# spectrum_4kHz_125Hz.net
KiCad netlist of a schematic drawn in Altium Designer
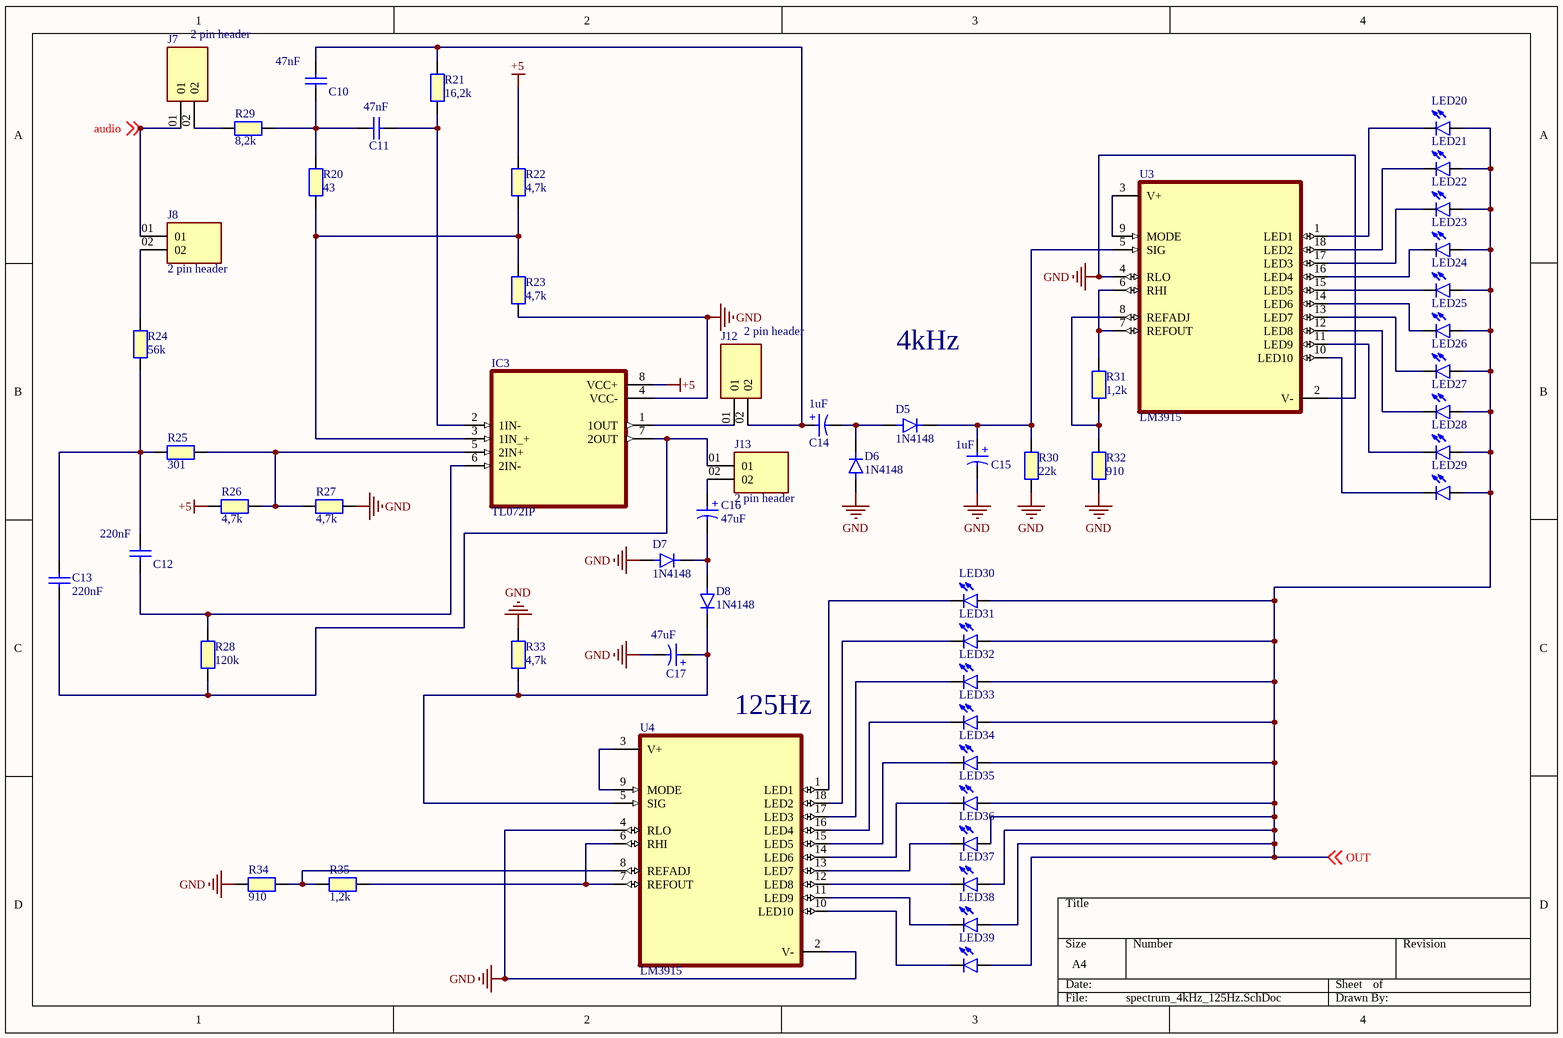
[diagram p0: spectrum_4kHz_125Hz.SchDoc]

(export (version "E")
  (design (tool "Eeschema 10.0.6"))
  (components
    (comp (ref "C10")
      (value "47nF")
      (footprint "CAPC2012X65N")
      (description "47nF ceramic")
      (fields
        (field (name "MANUFACTURER PART NUMBER") "885012004008")
        (field (name "MANUFACTURER") "Wurth Elektronik")
      )
      (libsource (lib "SpectrumComponents") (part "885012004008"))
    )
    (comp (ref "C11")
      (value "47nF")
      (footprint "CAPC2012X65N")
      (description "47nF ceramic")
      (fields
        (field (name "MANUFACTURER PART NUMBER") "885012004008")
        (field (name "MANUFACTURER") "Wurth Elektronik")
      )
      (libsource (lib "SpectrumComponents") (part "885012004008"))
    )
    (comp (ref "C12")
      (value "220nF")
      (footprint "CAPC2012X65N")
      (description "220nF ceramic")
      (fields
        (field (name "MANUFACTURER PART NUMBER") "885012004008")
        (field (name "MANUFACTURER") "Wurth Elektronik")
      )
      (libsource (lib "SpectrumComponents") (part "885012004008"))
    )
    (comp (ref "C13")
      (value "220nF")
      (footprint "CAPC2012X65N")
      (description "220nF ceramic")
      (fields
        (field (name "MANUFACTURER PART NUMBER") "885012004008")
        (field (name "MANUFACTURER") "Wurth Elektronik")
      )
      (libsource (lib "SpectrumComponents") (part "885012004008"))
    )
    (comp (ref "C14")
      (value "1uF")
      (footprint "WCAP-ATG8_D5H11")
      (description "Elco 1uF")
      (fields
        (field (name "MANUFACTURER PART NUMBER") "860010272005")
        (field (name "MANUFACTURER") "Wurth Elektronik")
      )
      (libsource (lib "SpectrumComponents") (part "860010272005"))
    )
    (comp (ref "C15")
      (value "1uF")
      (footprint "WCAP-ATG8_D5H11")
      (description "WCAP-ATG8 Aluminum Electrolytic Capacitor, Radial, THT, D5 x H11mm, 1uF, 10V")
      (fields
        (field (name "MANUFACTURER PART NUMBER") "860010272005")
        (field (name "MANUFACTURER") "Wurth Elektronik")
      )
      (libsource (lib "SpectrumComponents") (part "860010272005"))
    )
    (comp (ref "C16")
      (value "47uF")
      (footprint "WCAP-ATG8_D5H11")
      (description "Elco 47uF")
      (fields
        (field (name "MANUFACTURER PART NUMBER") "860010272005")
        (field (name "MANUFACTURER") "Wurth Elektronik")
      )
      (libsource (lib "SpectrumComponents") (part "860010272005"))
    )
    (comp (ref "C17")
      (value "47uF")
      (footprint "WCAP-ATG8_D5H11")
      (description "WCAP-ATG8 Aluminum Electrolytic Capacitor, Radial, THT, D5 x H11mm, 47µF, 10V")
      (fields
        (field (name "MANUFACTURER PART NUMBER") "860010272005")
        (field (name "MANUFACTURER") "Wurth Elektronik")
      )
      (libsource (lib "SpectrumComponents") (part "860010272005"))
    )
    (comp (ref "D5")
      (value "1N4148")
      (footprint "DIOAD829W49L456D191")
      (description "Diode Standard 75V 200mA Surface Mount SOD-523F")
      (fields (field (name "MF") "ON Semiconductor"))
      (libsource (lib "SpectrumComponents") (part "1N4148"))
    )
    (comp (ref "D6")
      (value "1N4148")
      (footprint "DIOAD829W49L456D191")
      (description "Diode Standard 75V 200mA Surface Mount SOD-523F")
      (fields (field (name "MF") "ON Semiconductor"))
      (libsource (lib "SpectrumComponents") (part "1N4148"))
    )
    (comp (ref "D7")
      (value "1N4148")
      (footprint "DIOAD829W49L456D191")
      (description "Diode Standard 75V 200mA Surface Mount SOD-523F")
      (fields (field (name "MF") "ON Semiconductor"))
      (libsource (lib "SpectrumComponents") (part "1N4148"))
    )
    (comp (ref "D8")
      (value "1N4148")
      (footprint "DIOAD829W49L456D191")
      (description "Diode Standard 75V 200mA Surface Mount SOD-523F")
      (fields (field (name "MF") "ON Semiconductor"))
      (libsource (lib "SpectrumComponents") (part "1N4148"))
    )
    (comp (ref "IC3")
      (value "TL072IP")
      (footprint "DIP794W45P254L959H508Q8")
      (description "Dual, 30-V, 3-MHz, high slew rate (13-V/Âµs), In to V+, JFET-input op amp")
      (fields (field (name "MF") "Texas Instruments"))
      (libsource (lib "SpectrumComponents") (part "TL072IP"))
    )
    (comp (ref "J7")
      (value "2 pin header")
      (footprint "SpectrumComponents:SAMTEC_HTSW-102-07-TM-S")
      (description "2 pin header Jumper")
      (fields (field (name "MP") "HTSW10207TMS") (field (name "MF") "Samtec"))
      (libsource (lib "") (part "2 pin header_1"))
    )
    (comp (ref "J8")
      (value "2 pin header")
      (footprint "SpectrumComponents:SAMTEC_HTSW-102-07-TM-S")
      (description "2 pin header Jumper")
      (fields (field (name "MP") "HTSW10207TMS") (field (name "MF") "Samtec"))
      (libsource (lib "SpectrumComponents") (part "2 pin header"))
    )
    (comp (ref "J12")
      (value "2 pin header")
      (footprint "SpectrumComponents:SAMTEC_HTSW-102-07-TM-S")
      (description "2 pin header Jumper")
      (fields (field (name "MP") "HTSW10207TMS") (field (name "MF") "Samtec"))
      (libsource (lib "") (part "2 pin header_1"))
    )
    (comp (ref "J13")
      (value "2 pin header")
      (footprint "SpectrumComponents:SAMTEC_HTSW-102-07-TM-S")
      (description "2 pin header Jumper")
      (fields (field (name "MP") "HTSW10207TMS") (field (name "MF") "Samtec"))
      (libsource (lib "SpectrumComponents") (part "2 pin header"))
    )
    (comp (ref "LED20")
      (value "LED 2x3x4")
      (footprint "LED 2x3x4mm")
      (description "Green 569nm LED Indication - Discrete 1.9V Radial")
      (fields (field (name "MP") "TLLG4400") (field (name "MF") "Vishay Semiconductors"))
      (libsource (lib "SpectrumComponents") (part "LED 2x3x4"))
    )
    (comp (ref "LED21")
      (value "LED 2x3x4")
      (footprint "LED 2x3x4mm")
      (description "Green 569nm LED Indication - Discrete 1.9V Radial")
      (fields (field (name "MP") "TLLG4400") (field (name "MF") "Vishay Semiconductors"))
      (libsource (lib "SpectrumComponents") (part "LED 2x3x4"))
    )
    (comp (ref "LED22")
      (value "LED 2x3x4")
      (footprint "LED 2x3x4mm")
      (description "Green 569nm LED Indication - Discrete 1.9V Radial")
      (fields (field (name "MP") "TLLG4400") (field (name "MF") "Vishay Semiconductors"))
      (libsource (lib "SpectrumComponents") (part "LED 2x3x4"))
    )
    (comp (ref "LED23")
      (value "LED 2x3x4")
      (footprint "LED 2x3x4mm")
      (description "Green 569nm LED Indication - Discrete 1.9V Radial")
      (fields (field (name "MP") "TLLG4400") (field (name "MF") "Vishay Semiconductors"))
      (libsource (lib "SpectrumComponents") (part "LED 2x3x4"))
    )
    (comp (ref "LED24")
      (value "LED 2x3x4")
      (footprint "LED 2x3x4mm")
      (description "Green 569nm LED Indication - Discrete 1.9V Radial")
      (fields (field (name "MP") "TLLG4400") (field (name "MF") "Vishay Semiconductors"))
      (libsource (lib "SpectrumComponents") (part "LED 2x3x4"))
    )
    (comp (ref "LED25")
      (value "LED 2x3x4")
      (footprint "LED 2x3x4mm")
      (description "Green 569nm LED Indication - Discrete 1.9V Radial")
      (fields (field (name "MP") "TLLG4400") (field (name "MF") "Vishay Semiconductors"))
      (libsource (lib "SpectrumComponents") (part "LED 2x3x4"))
    )
    (comp (ref "LED26")
      (value "LED 2x3x4")
      (footprint "LED 2x3x4mm")
      (description "Green 569nm LED Indication - Discrete 1.9V Radial")
      (fields (field (name "MP") "TLLG4400") (field (name "MF") "Vishay Semiconductors"))
      (libsource (lib "SpectrumComponents") (part "LED 2x3x4"))
    )
    (comp (ref "LED27")
      (value "LED 2x3x4")
      (footprint "LED 2x3x4mm")
      (description "Green 569nm LED Indication - Discrete 1.9V Radial")
      (fields (field (name "MP") "TLLG4400") (field (name "MF") "Vishay Semiconductors"))
      (libsource (lib "SpectrumComponents") (part "LED 2x3x4"))
    )
    (comp (ref "LED28")
      (value "LED 2x3x4")
      (footprint "LED 2x3x4mm")
      (description "Green 569nm LED Indication - Discrete 1.9V Radial")
      (fields (field (name "MP") "TLLG4400") (field (name "MF") "Vishay Semiconductors"))
      (libsource (lib "SpectrumComponents") (part "LED 2x3x4"))
    )
    (comp (ref "LED29")
      (value "LED 2x3x4")
      (footprint "LED 2x3x4mm")
      (description "Green 569nm LED Indication - Discrete 1.9V Radial")
      (fields (field (name "MP") "TLLG4400") (field (name "MF") "Vishay Semiconductors"))
      (libsource (lib "SpectrumComponents") (part "LED 2x3x4"))
    )
    (comp (ref "LED30")
      (value "LED 2x3x4")
      (footprint "LED 2x3x4mm")
      (description "Green 569nm LED Indication - Discrete 1.9V Radial")
      (fields (field (name "MP") "TLLG4400") (field (name "MF") "Vishay Semiconductors"))
      (libsource (lib "SpectrumComponents") (part "LED 2x3x4"))
    )
    (comp (ref "LED31")
      (value "LED 2x3x4")
      (footprint "LED 2x3x4mm")
      (description "Green 569nm LED Indication - Discrete 1.9V Radial")
      (fields (field (name "MP") "TLLG4400") (field (name "MF") "Vishay Semiconductors"))
      (libsource (lib "SpectrumComponents") (part "LED 2x3x4"))
    )
    (comp (ref "LED32")
      (value "LED 2x3x4")
      (footprint "LED 2x3x4mm")
      (description "Green 569nm LED Indication - Discrete 1.9V Radial")
      (fields (field (name "MP") "TLLG4400") (field (name "MF") "Vishay Semiconductors"))
      (libsource (lib "SpectrumComponents") (part "LED 2x3x4"))
    )
    (comp (ref "LED33")
      (value "LED 2x3x4")
      (footprint "LED 2x3x4mm")
      (description "Green 569nm LED Indication - Discrete 1.9V Radial")
      (fields (field (name "MP") "TLLG4400") (field (name "MF") "Vishay Semiconductors"))
      (libsource (lib "SpectrumComponents") (part "LED 2x3x4"))
    )
    (comp (ref "LED34")
      (value "LED 2x3x4")
      (footprint "LED 2x3x4mm")
      (description "Green 569nm LED Indication - Discrete 1.9V Radial")
      (fields (field (name "MP") "TLLG4400") (field (name "MF") "Vishay Semiconductors"))
      (libsource (lib "SpectrumComponents") (part "LED 2x3x4"))
    )
    (comp (ref "LED35")
      (value "LED 2x3x4")
      (footprint "LED 2x3x4mm")
      (description "Green 569nm LED Indication - Discrete 1.9V Radial")
      (fields (field (name "MP") "TLLG4400") (field (name "MF") "Vishay Semiconductors"))
      (libsource (lib "SpectrumComponents") (part "LED 2x3x4"))
    )
    (comp (ref "LED36")
      (value "LED 2x3x4")
      (footprint "LED 2x3x4mm")
      (description "Green 569nm LED Indication - Discrete 1.9V Radial")
      (fields (field (name "MP") "TLLG4400") (field (name "MF") "Vishay Semiconductors"))
      (libsource (lib "SpectrumComponents") (part "LED 2x3x4"))
    )
    (comp (ref "LED37")
      (value "LED 2x3x4")
      (footprint "LED 2x3x4mm")
      (description "Green 569nm LED Indication - Discrete 1.9V Radial")
      (fields (field (name "MP") "TLLG4400") (field (name "MF") "Vishay Semiconductors"))
      (libsource (lib "SpectrumComponents") (part "LED 2x3x4"))
    )
    (comp (ref "LED38")
      (value "LED 2x3x4")
      (footprint "LED 2x3x4mm")
      (description "Green 569nm LED Indication - Discrete 1.9V Radial")
      (fields (field (name "MP") "TLLG4400") (field (name "MF") "Vishay Semiconductors"))
      (libsource (lib "SpectrumComponents") (part "LED 2x3x4"))
    )
    (comp (ref "LED39")
      (value "LED 2x3x4")
      (footprint "LED 2x3x4mm")
      (description "Green 569nm LED Indication - Discrete 1.9V Radial")
      (fields (field (name "MP") "TLLG4400") (field (name "MF") "Vishay Semiconductors"))
      (libsource (lib "SpectrumComponents") (part "LED 2x3x4"))
    )
    (comp (ref "R20")
      (value "43")
      (footprint "RESC2012X50N")
      (description "43Ohm Resistor 0805")
      (fields (field (name "PART NUMBER") "TNPW080510K0BETA") (field (name "MANUFACTURER") "Vishay Dale"))
      (libsource (lib "") (part "RESISTOR 0805_1"))
    )
    (comp (ref "R21")
      (value "16,2k")
      (footprint "RESC2012X50N")
      (description "16,2k Resistor 0805")
      (fields (field (name "PART NUMBER") "TNPW080510K0BETA") (field (name "MANUFACTURER") "Vishay Dale"))
      (libsource (lib "") (part "RESISTOR 0805_1"))
    )
    (comp (ref "R22")
      (value "4,7k")
      (footprint "RESC2012X50N")
      (description "4,7k Resistor 0805")
      (fields (field (name "PART NUMBER") "TNPW080510K0BETA") (field (name "MANUFACTURER") "Vishay Dale"))
      (libsource (lib "") (part "RESISTOR 0805_1"))
    )
    (comp (ref "R23")
      (value "4,7k")
      (footprint "RESC2012X50N")
      (description "4,7k Resistor 0805")
      (fields (field (name "PART NUMBER") "TNPW080510K0BETA") (field (name "MANUFACTURER") "Vishay Dale"))
      (libsource (lib "") (part "RESISTOR 0805_1"))
    )
    (comp (ref "R24")
      (value "56k")
      (footprint "RESC2012X50N")
      (description "75k Resistor 0805")
      (fields (field (name "PART NUMBER") "TNPW080510K0BETA") (field (name "MANUFACTURER") "Vishay Dale"))
      (libsource (lib "") (part "RESISTOR 0805_1"))
    )
    (comp (ref "R25")
      (value "301")
      (footprint "RESC2012X50N")
      (description "301 Resistor 0805")
      (fields (field (name "PART NUMBER") "TNPW080510K0BETA") (field (name "MANUFACTURER") "Vishay Dale"))
      (libsource (lib "") (part "RESISTOR 0805_2"))
    )
    (comp (ref "R26")
      (value "4,7k")
      (footprint "RESC2012X50N")
      (description "4,7k Resistor 0805")
      (fields (field (name "PART NUMBER") "TNPW080510K0BETA") (field (name "MANUFACTURER") "Vishay Dale"))
      (libsource (lib "") (part "RESISTOR 0805_2"))
    )
    (comp (ref "R27")
      (value "4,7k")
      (footprint "RESC2012X50N")
      (description "4,7k Resistor 0805")
      (fields (field (name "PART NUMBER") "TNPW080510K0BETA") (field (name "MANUFACTURER") "Vishay Dale"))
      (libsource (lib "") (part "RESISTOR 0805_3"))
    )
    (comp (ref "R28")
      (value "120k")
      (footprint "RESC2012X50N")
      (description "120k Resistor 0805")
      (fields (field (name "PART NUMBER") "TNPW080510K0BETA") (field (name "MANUFACTURER") "Vishay Dale"))
      (libsource (lib "") (part "RESISTOR 0805_1"))
    )
    (comp (ref "R29")
      (value "8,2k")
      (footprint "RESC2012X50N")
      (description "8,2k Resistor 0805")
      (fields (field (name "PART NUMBER") "TNPW080510K0BETA") (field (name "MANUFACTURER") "Vishay Dale"))
      (libsource (lib "") (part "RESISTOR 0805_3"))
    )
    (comp (ref "R30")
      (value "22k")
      (footprint "RESC2012X50N")
      (description "22k Resistor 0805")
      (fields (field (name "PART NUMBER") "TNPW080510K0BETA") (field (name "MANUFACTURER") "Vishay Dale"))
      (libsource (lib "") (part "RESISTOR 0805_1"))
    )
    (comp (ref "R31")
      (value "1,2k")
      (footprint "RESC2012X50N")
      (description "1,2k Resistor 0805")
      (fields (field (name "PART NUMBER") "TNPW080510K0BETA") (field (name "MANUFACTURER") "Vishay Dale"))
      (libsource (lib "SpectrumComponents") (part "RESISTOR 0805"))
    )
    (comp (ref "R32")
      (value "910")
      (footprint "RESC2012X50N")
      (description "910 Resistor 0805")
      (fields (field (name "PART NUMBER") "TNPW080510K0BETA") (field (name "MANUFACTURER") "Vishay Dale"))
      (libsource (lib "SpectrumComponents") (part "RESISTOR 0805"))
    )
    (comp (ref "R33")
      (value "4,7k")
      (footprint "RESC2012X50N")
      (description "4,7k Resistor 0805")
      (fields (field (name "PART NUMBER") "TNPW080510K0BETA") (field (name "MANUFACTURER") "Vishay Dale"))
      (libsource (lib "SpectrumComponents") (part "RESISTOR 0805"))
    )
    (comp (ref "R34")
      (value "910")
      (footprint "RESC2012X50N")
      (description "910 Resistor 0805")
      (fields (field (name "PART NUMBER") "TNPW080510K0BETA") (field (name "MANUFACTURER") "Vishay Dale"))
      (libsource (lib "") (part "RESISTOR 0805_2"))
    )
    (comp (ref "R35")
      (value "1,2k")
      (footprint "RESC2012X50N")
      (description "1,2k Resistor 0805")
      (fields (field (name "PART NUMBER") "TNPW080510K0BETA") (field (name "MANUFACTURER") "Vishay Dale"))
      (libsource (lib "") (part "RESISTOR 0805_2"))
    )
    (comp (ref "U3")
      (value "LM3915")
      (footprint "SpectrumComponents:DIP952W45P254L2336H533Q18")
      (fields (field (name "MP") "LM3914N-1"))
      (libsource (lib "SpectrumComponents") (part "LM3915"))
    )
    (comp (ref "U4")
      (value "LM3915")
      (footprint "SpectrumComponents:DIP952W45P254L2336H533Q18")
      (fields (field (name "MP") "LM3914N-1"))
      (libsource (lib "SpectrumComponents") (part "LM3915"))
    )
  )
  (nets
    (net (code "1") (name "+5") (class "Default")
      (node (ref "IC3") (pin "8") (pinfunction "VCC+_8") (pintype "power_in"))
      (node (ref "R22") (pin "2") (pinfunction "2_2") (pintype "passive"))
      (node (ref "R26") (pin "2") (pinfunction "2_2") (pintype "passive"))
    )
    (net (code "2") (name "GND") (class "Default")
      (node (ref "C15") (pin "2") (pinfunction "N_2") (pintype "passive"))
      (node (ref "C17") (pin "2") (pinfunction "N_2") (pintype "passive"))
      (node (ref "D6") (pin "A") (pinfunction "A_A") (pintype "passive"))
      (node (ref "D7") (pin "A") (pinfunction "A_A") (pintype "passive"))
      (node (ref "IC3") (pin "4") (pinfunction "VCC-_4") (pintype "power_in"))
      (node (ref "R23") (pin "1") (pinfunction "1_1") (pintype "passive"))
      (node (ref "R27") (pin "2") (pinfunction "2_2") (pintype "passive"))
      (node (ref "R30") (pin "1") (pinfunction "1_1") (pintype "passive"))
      (node (ref "R32") (pin "2") (pinfunction "2_2") (pintype "passive"))
      (node (ref "R33") (pin "1") (pinfunction "1_1") (pintype "passive"))
      (node (ref "R34") (pin "2") (pinfunction "2_2") (pintype "passive"))
      (node (ref "U3") (pin "2") (pinfunction "V-_2") (pintype "power_in"))
      (node (ref "U3") (pin "4") (pinfunction "RLO_4") (pintype "bidirectional"))
      (node (ref "U4") (pin "2") (pinfunction "V-_2") (pintype "power_in"))
      (node (ref "U4") (pin "4") (pinfunction "RLO_4") (pintype "bidirectional"))
    )
    (net (code "3") (name "Net-(C10-Pad1)") (class "Default")
      (node (ref "C10") (pin "1") (pinfunction "1_1") (pintype "passive"))
      (node (ref "C11") (pin "1") (pinfunction "1_1") (pintype "passive"))
      (node (ref "R20") (pin "2") (pinfunction "2_2") (pintype "passive"))
      (node (ref "R29") (pin "2") (pinfunction "2_2") (pintype "passive"))
    )
    (net (code "4") (name "Net-(C12-Pad2)") (class "Default")
      (node (ref "C12") (pin "2") (pinfunction "2_2") (pintype "passive"))
      (node (ref "C13") (pin "2") (pinfunction "2_2") (pintype "passive"))
      (node (ref "R24") (pin "1") (pinfunction "1_1") (pintype "passive"))
      (node (ref "R25") (pin "2") (pinfunction "2_2") (pintype "passive"))
    )
    (net (code "5") (name "Net-(C14-N)") (class "Default")
      (node (ref "C14") (pin "2") (pinfunction "N_2") (pintype "passive"))
      (node (ref "D5") (pin "A") (pinfunction "A_A") (pintype "passive"))
      (node (ref "D6") (pin "C") (pinfunction "C_C") (pintype "passive"))
    )
    (net (code "6") (name "Net-(C14-P)") (class "Default")
      (node (ref "C10") (pin "2") (pinfunction "2_2") (pintype "passive"))
      (node (ref "C14") (pin "1") (pinfunction "P_1") (pintype "passive"))
      (node (ref "J12") (pin "02") (pinfunction "02_02") (pintype "passive"))
      (node (ref "R21") (pin "2") (pinfunction "2_2") (pintype "passive"))
    )
    (net (code "7") (name "Net-(C15-P)") (class "Default")
      (node (ref "C15") (pin "1") (pinfunction "P_1") (pintype "passive"))
      (node (ref "D5") (pin "C") (pinfunction "C_C") (pintype "passive"))
      (node (ref "R30") (pin "2") (pinfunction "2_2") (pintype "passive"))
      (node (ref "U3") (pin "5") (pinfunction "SIG_5") (pintype "input"))
    )
    (net (code "8") (name "Net-(C16-N)") (class "Default")
      (node (ref "C16") (pin "2") (pinfunction "N_2") (pintype "passive"))
      (node (ref "D7") (pin "C") (pinfunction "C_C") (pintype "passive"))
      (node (ref "D8") (pin "A") (pinfunction "A_A") (pintype "passive"))
    )
    (net (code "9") (name "Net-(C16-P)") (class "Default")
      (node (ref "C16") (pin "1") (pinfunction "P_1") (pintype "passive"))
      (node (ref "J13") (pin "02") (pinfunction "02_02") (pintype "passive"))
    )
    (net (code "10") (name "Net-(C17-P)") (class "Default")
      (node (ref "C17") (pin "1") (pinfunction "P_1") (pintype "passive"))
      (node (ref "D8") (pin "C") (pinfunction "C_C") (pintype "passive"))
      (node (ref "R33") (pin "2") (pinfunction "2_2") (pintype "passive"))
      (node (ref "U4") (pin "5") (pinfunction "SIG_5") (pintype "input"))
    )
    (net (code "11") (name "Net-(IC3-1IN-)") (class "Default")
      (node (ref "C11") (pin "2") (pinfunction "2_2") (pintype "passive"))
      (node (ref "IC3") (pin "2") (pinfunction "1IN-_2") (pintype "input"))
      (node (ref "R21") (pin "1") (pinfunction "1_1") (pintype "passive"))
    )
    (net (code "12") (name "Net-(IC3-1IN_+)") (class "Default")
      (node (ref "IC3") (pin "3") (pinfunction "1IN_+_3") (pintype "input"))
      (node (ref "R20") (pin "1") (pinfunction "1_1") (pintype "passive"))
      (node (ref "R22") (pin "1") (pinfunction "1_1") (pintype "passive"))
      (node (ref "R23") (pin "2") (pinfunction "2_2") (pintype "passive"))
    )
    (net (code "13") (name "Net-(IC3-1OUT)") (class "Default")
      (node (ref "IC3") (pin "1") (pinfunction "1OUT_1") (pintype "output"))
      (node (ref "J12") (pin "01") (pinfunction "01_01") (pintype "passive"))
    )
    (net (code "14") (name "Net-(IC3-2IN+)") (class "Default")
      (node (ref "IC3") (pin "5") (pinfunction "2IN+_5") (pintype "input"))
      (node (ref "R25") (pin "1") (pinfunction "1_1") (pintype "passive"))
      (node (ref "R26") (pin "1") (pinfunction "1_1") (pintype "passive"))
      (node (ref "R27") (pin "1") (pinfunction "1_1") (pintype "passive"))
    )
    (net (code "15") (name "Net-(IC3-2IN-)") (class "Default")
      (node (ref "C12") (pin "1") (pinfunction "1_1") (pintype "passive"))
      (node (ref "IC3") (pin "6") (pinfunction "2IN-_6") (pintype "input"))
      (node (ref "R28") (pin "2") (pinfunction "2_2") (pintype "passive"))
    )
    (net (code "16") (name "Net-(IC3-2OUT)") (class "Default")
      (node (ref "C13") (pin "1") (pinfunction "1_1") (pintype "passive"))
      (node (ref "IC3") (pin "7") (pinfunction "2OUT_7") (pintype "output"))
      (node (ref "J13") (pin "01") (pinfunction "01_01") (pintype "passive"))
      (node (ref "R28") (pin "1") (pinfunction "1_1") (pintype "passive"))
    )
    (net (code "17") (name "Net-(J7-Pad02)") (class "Default")
      (node (ref "J7") (pin "02") (pinfunction "02_02") (pintype "passive"))
      (node (ref "R29") (pin "1") (pinfunction "1_1") (pintype "passive"))
    )
    (net (code "18") (name "Net-(J8-Pad02)") (class "Default")
      (node (ref "J8") (pin "02") (pinfunction "02_02") (pintype "passive"))
      (node (ref "R24") (pin "2") (pinfunction "2_2") (pintype "passive"))
    )
    (net (code "19") (name "Net-(LED20-C)") (class "Default")
      (node (ref "LED20") (pin "K") (pinfunction "C_K") (pintype "passive"))
      (node (ref "U3") (pin "1") (pinfunction "LED1_1") (pintype "bidirectional"))
    )
    (net (code "20") (name "Net-(LED21-C)") (class "Default")
      (node (ref "LED21") (pin "K") (pinfunction "C_K") (pintype "passive"))
      (node (ref "U3") (pin "18") (pinfunction "LED2_18") (pintype "bidirectional"))
    )
    (net (code "21") (name "Net-(LED22-C)") (class "Default")
      (node (ref "LED22") (pin "K") (pinfunction "C_K") (pintype "passive"))
      (node (ref "U3") (pin "17") (pinfunction "LED3_17") (pintype "bidirectional"))
    )
    (net (code "22") (name "Net-(LED23-C)") (class "Default")
      (node (ref "LED23") (pin "K") (pinfunction "C_K") (pintype "passive"))
      (node (ref "U3") (pin "16") (pinfunction "LED4_16") (pintype "bidirectional"))
    )
    (net (code "23") (name "Net-(LED24-C)") (class "Default")
      (node (ref "LED24") (pin "K") (pinfunction "C_K") (pintype "passive"))
      (node (ref "U3") (pin "15") (pinfunction "LED5_15") (pintype "bidirectional"))
    )
    (net (code "24") (name "Net-(LED25-C)") (class "Default")
      (node (ref "LED25") (pin "K") (pinfunction "C_K") (pintype "passive"))
      (node (ref "U3") (pin "14") (pinfunction "LED6_14") (pintype "bidirectional"))
    )
    (net (code "25") (name "Net-(LED26-C)") (class "Default")
      (node (ref "LED26") (pin "K") (pinfunction "C_K") (pintype "passive"))
      (node (ref "U3") (pin "13") (pinfunction "LED7_13") (pintype "bidirectional"))
    )
    (net (code "26") (name "Net-(LED27-C)") (class "Default")
      (node (ref "LED27") (pin "K") (pinfunction "C_K") (pintype "passive"))
      (node (ref "U3") (pin "12") (pinfunction "LED8_12") (pintype "bidirectional"))
    )
    (net (code "27") (name "Net-(LED28-C)") (class "Default")
      (node (ref "LED28") (pin "K") (pinfunction "C_K") (pintype "passive"))
      (node (ref "U3") (pin "11") (pinfunction "LED9_11") (pintype "bidirectional"))
    )
    (net (code "28") (name "Net-(LED29-C)") (class "Default")
      (node (ref "LED29") (pin "K") (pinfunction "C_K") (pintype "passive"))
      (node (ref "U3") (pin "10") (pinfunction "LED10_10") (pintype "bidirectional"))
    )
    (net (code "29") (name "Net-(LED30-C)") (class "Default")
      (node (ref "LED30") (pin "K") (pinfunction "C_K") (pintype "passive"))
      (node (ref "U4") (pin "1") (pinfunction "LED1_1") (pintype "bidirectional"))
    )
    (net (code "30") (name "Net-(LED31-C)") (class "Default")
      (node (ref "LED31") (pin "K") (pinfunction "C_K") (pintype "passive"))
      (node (ref "U4") (pin "18") (pinfunction "LED2_18") (pintype "bidirectional"))
    )
    (net (code "31") (name "Net-(LED32-C)") (class "Default")
      (node (ref "LED32") (pin "K") (pinfunction "C_K") (pintype "passive"))
      (node (ref "U4") (pin "17") (pinfunction "LED3_17") (pintype "bidirectional"))
    )
    (net (code "32") (name "Net-(LED33-C)") (class "Default")
      (node (ref "LED33") (pin "K") (pinfunction "C_K") (pintype "passive"))
      (node (ref "U4") (pin "16") (pinfunction "LED4_16") (pintype "bidirectional"))
    )
    (net (code "33") (name "Net-(LED34-C)") (class "Default")
      (node (ref "LED34") (pin "K") (pinfunction "C_K") (pintype "passive"))
      (node (ref "U4") (pin "15") (pinfunction "LED5_15") (pintype "bidirectional"))
    )
    (net (code "34") (name "Net-(LED35-C)") (class "Default")
      (node (ref "LED35") (pin "K") (pinfunction "C_K") (pintype "passive"))
      (node (ref "U4") (pin "14") (pinfunction "LED6_14") (pintype "bidirectional"))
    )
    (net (code "35") (name "Net-(LED36-C)") (class "Default")
      (node (ref "LED36") (pin "K") (pinfunction "C_K") (pintype "passive"))
      (node (ref "U4") (pin "13") (pinfunction "LED7_13") (pintype "bidirectional"))
    )
    (net (code "36") (name "Net-(LED37-C)") (class "Default")
      (node (ref "LED37") (pin "K") (pinfunction "C_K") (pintype "passive"))
      (node (ref "U4") (pin "12") (pinfunction "LED8_12") (pintype "bidirectional"))
    )
    (net (code "37") (name "Net-(LED38-C)") (class "Default")
      (node (ref "LED38") (pin "K") (pinfunction "C_K") (pintype "passive"))
      (node (ref "U4") (pin "11") (pinfunction "LED9_11") (pintype "bidirectional"))
    )
    (net (code "38") (name "Net-(LED39-C)") (class "Default")
      (node (ref "LED39") (pin "K") (pinfunction "C_K") (pintype "passive"))
      (node (ref "U4") (pin "10") (pinfunction "LED10_10") (pintype "bidirectional"))
    )
    (net (code "39") (name "Net-(U3-MODE)") (class "Default")
      (node (ref "U3") (pin "3") (pinfunction "V+_3") (pintype "power_in"))
      (node (ref "U3") (pin "9") (pinfunction "MODE_9") (pintype "input"))
    )
    (net (code "40") (name "Net-(U3-REFADJ)") (class "Default")
      (node (ref "R31") (pin "2") (pinfunction "2_2") (pintype "passive"))
      (node (ref "R32") (pin "1") (pinfunction "1_1") (pintype "passive"))
      (node (ref "U3") (pin "8") (pinfunction "REFADJ_8") (pintype "bidirectional"))
    )
    (net (code "41") (name "Net-(U3-REFOUT)") (class "Default")
      (node (ref "R31") (pin "1") (pinfunction "1_1") (pintype "passive"))
      (node (ref "U3") (pin "6") (pinfunction "RHI_6") (pintype "bidirectional"))
      (node (ref "U3") (pin "7") (pinfunction "REFOUT_7") (pintype "bidirectional"))
    )
    (net (code "42") (name "Net-(U4-MODE)") (class "Default")
      (node (ref "U4") (pin "3") (pinfunction "V+_3") (pintype "power_in"))
      (node (ref "U4") (pin "9") (pinfunction "MODE_9") (pintype "input"))
    )
    (net (code "43") (name "Net-(U4-REFADJ)") (class "Default")
      (node (ref "R34") (pin "1") (pinfunction "1_1") (pintype "passive"))
      (node (ref "R35") (pin "2") (pinfunction "2_2") (pintype "passive"))
      (node (ref "U4") (pin "8") (pinfunction "REFADJ_8") (pintype "bidirectional"))
    )
    (net (code "44") (name "Net-(U4-REFOUT)") (class "Default")
      (node (ref "R35") (pin "1") (pinfunction "1_1") (pintype "passive"))
      (node (ref "U4") (pin "6") (pinfunction "RHI_6") (pintype "bidirectional"))
      (node (ref "U4") (pin "7") (pinfunction "REFOUT_7") (pintype "bidirectional"))
    )
    (net (code "45") (name "OUT") (class "Default")
      (node (ref "LED20") (pin "A") (pinfunction "A_A") (pintype "passive"))
      (node (ref "LED21") (pin "A") (pinfunction "A_A") (pintype "passive"))
      (node (ref "LED22") (pin "A") (pinfunction "A_A") (pintype "passive"))
      (node (ref "LED23") (pin "A") (pinfunction "A_A") (pintype "passive"))
      (node (ref "LED24") (pin "A") (pinfunction "A_A") (pintype "passive"))
      (node (ref "LED25") (pin "A") (pinfunction "A_A") (pintype "passive"))
      (node (ref "LED26") (pin "A") (pinfunction "A_A") (pintype "passive"))
      (node (ref "LED27") (pin "A") (pinfunction "A_A") (pintype "passive"))
      (node (ref "LED28") (pin "A") (pinfunction "A_A") (pintype "passive"))
      (node (ref "LED29") (pin "A") (pinfunction "A_A") (pintype "passive"))
      (node (ref "LED30") (pin "A") (pinfunction "A_A") (pintype "passive"))
      (node (ref "LED31") (pin "A") (pinfunction "A_A") (pintype "passive"))
      (node (ref "LED32") (pin "A") (pinfunction "A_A") (pintype "passive"))
      (node (ref "LED33") (pin "A") (pinfunction "A_A") (pintype "passive"))
      (node (ref "LED34") (pin "A") (pinfunction "A_A") (pintype "passive"))
      (node (ref "LED35") (pin "A") (pinfunction "A_A") (pintype "passive"))
      (node (ref "LED36") (pin "A") (pinfunction "A_A") (pintype "passive"))
      (node (ref "LED37") (pin "A") (pinfunction "A_A") (pintype "passive"))
      (node (ref "LED38") (pin "A") (pinfunction "A_A") (pintype "passive"))
      (node (ref "LED39") (pin "A") (pinfunction "A_A") (pintype "passive"))
    )
    (net (code "46") (name "audio") (class "Default")
      (node (ref "J7") (pin "01") (pinfunction "01_01") (pintype "passive"))
      (node (ref "J8") (pin "01") (pinfunction "01_01") (pintype "passive"))
    )
  )
)
